# irda-usb-transmitter-V3.net
KiCad netlist of a schematic drawn in EAGLE
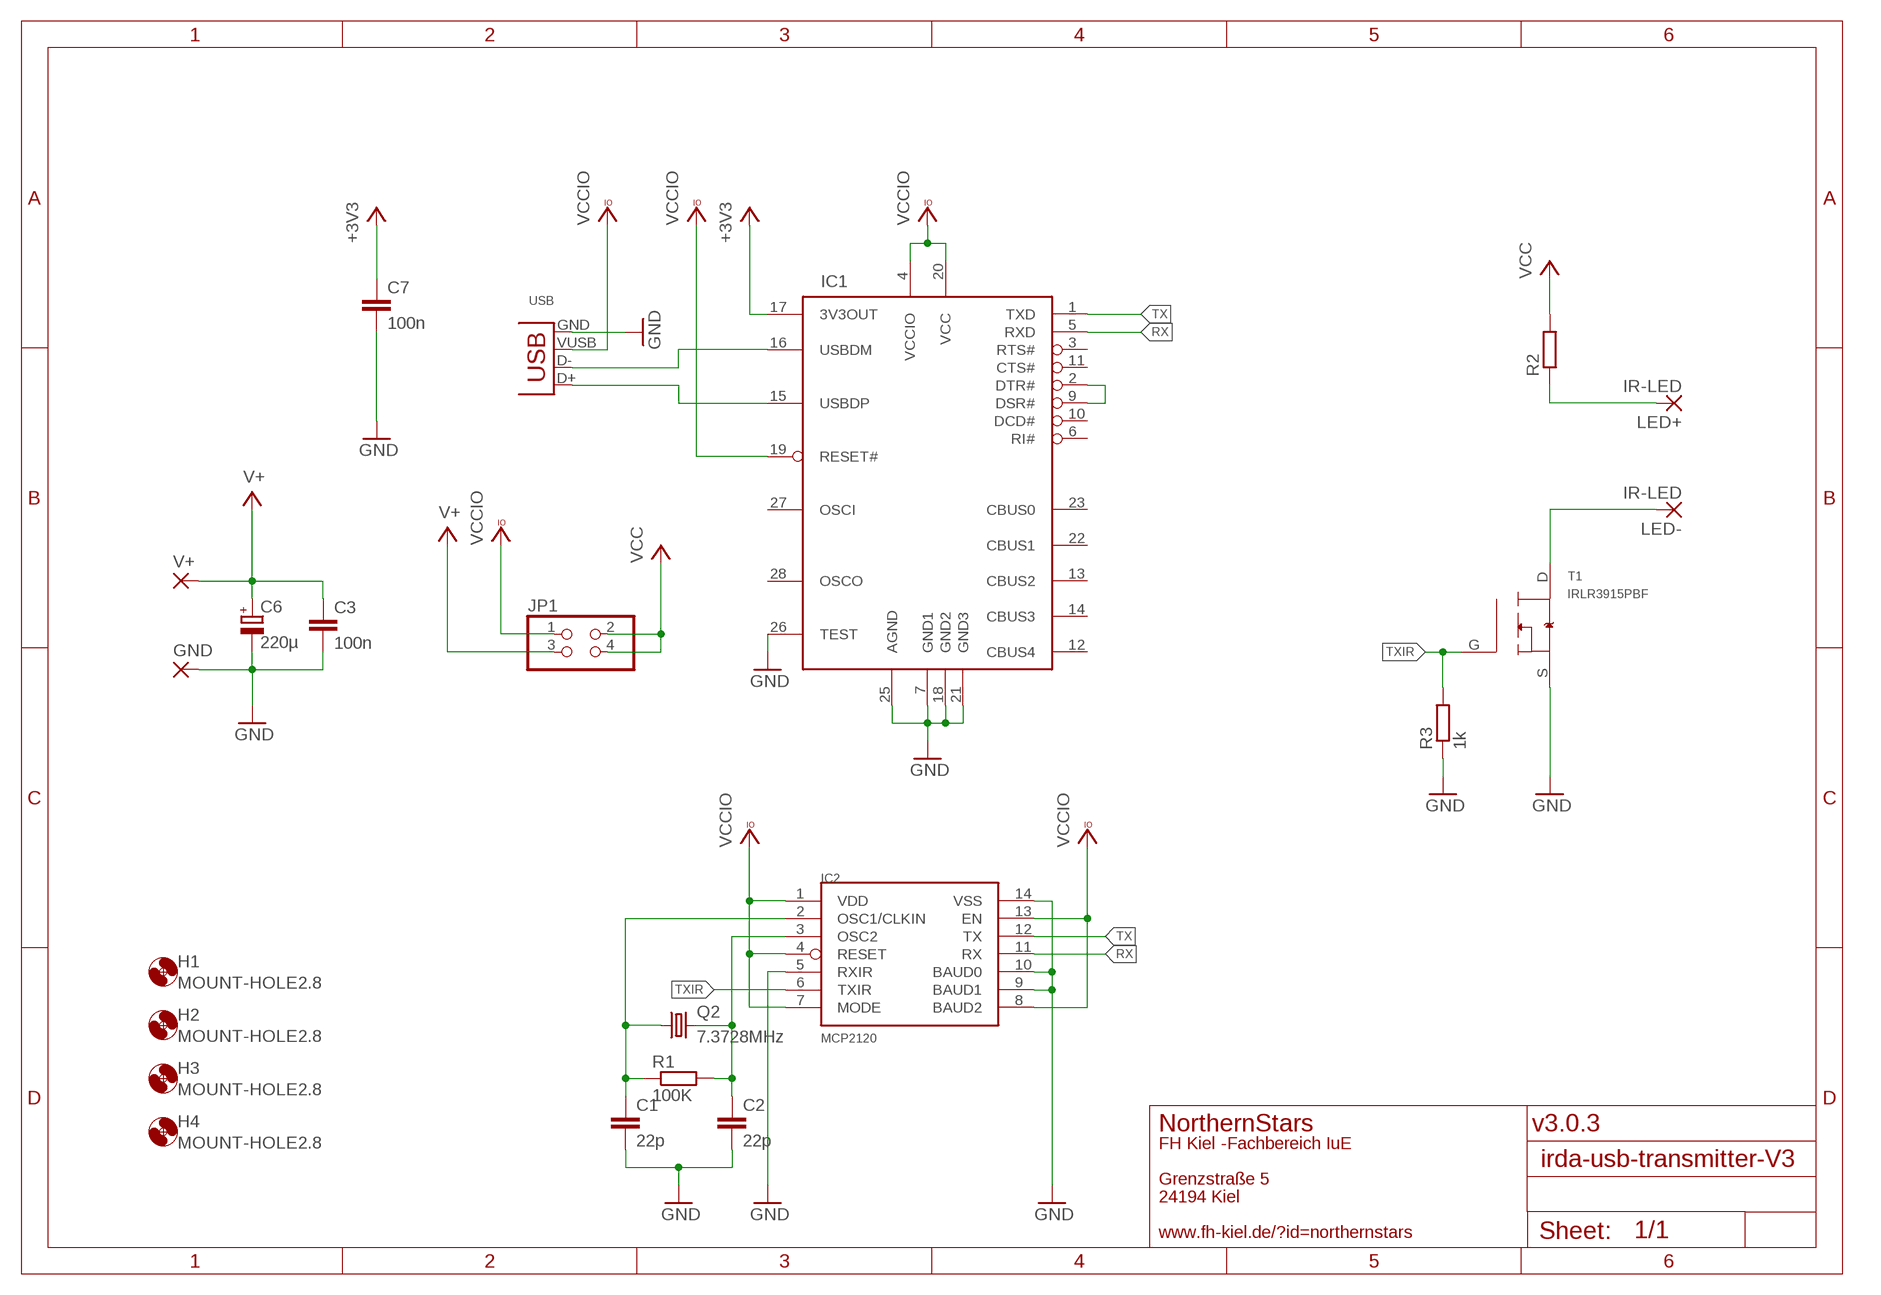
[diagram p0: schematic, sheet 1]

(export (version "E")
  (design (tool "Eeschema 10.0.6"))
  (components
    (comp (ref "C1")
      (value "22p")
      (footprint "eagle-import:C0805")
      (libsource (lib "eagle-import") (part "C-EUC0805"))
    )
    (comp (ref "C2")
      (value "22p")
      (footprint "eagle-import:C0805")
      (libsource (lib "eagle-import") (part "C-EUC0805"))
    )
    (comp (ref "C3")
      (value "100n")
      (footprint "eagle-import:C1206")
      (libsource (lib "eagle-import") (part "C-EUC1206"))
    )
    (comp (ref "C6")
      (value "220µ")
      (footprint "eagle-import:E3,5-8")
      (libsource (lib "eagle-import") (part "CPOL-EUE3.5-8"))
    )
    (comp (ref "C7")
      (value "100n")
      (footprint "eagle-import:C1206")
      (libsource (lib "eagle-import") (part "C-EUC1206"))
    )
    (comp (ref "GND")
      (value "SMD5")
      (footprint "eagle-import:SMD2,54-5,08")
      (libsource (lib "eagle-import") (part "SMD5"))
    )
    (comp (ref "H1")
      (value "MOUNT-HOLE2.8")
      (footprint "eagle-import:2,8")
      (libsource (lib "eagle-import") (part "MOUNT-HOLE2.8"))
    )
    (comp (ref "H2")
      (value "MOUNT-HOLE2.8")
      (footprint "eagle-import:2,8")
      (libsource (lib "eagle-import") (part "MOUNT-HOLE2.8"))
    )
    (comp (ref "H3")
      (value "MOUNT-HOLE2.8")
      (footprint "eagle-import:2,8")
      (libsource (lib "eagle-import") (part "MOUNT-HOLE2.8"))
    )
    (comp (ref "H4")
      (value "MOUNT-HOLE2.8")
      (footprint "eagle-import:2,8")
      (libsource (lib "eagle-import") (part "MOUNT-HOLE2.8"))
    )
    (comp (ref "IC1")
      (value "FT232RL")
      (footprint "eagle-import:SSOP28DB")
      (libsource (lib "eagle-import") (part "FT232RL"))
    )
    (comp (ref "IC2")
      (value "MCP2120")
      (footprint "eagle-import:SO-14")
      (libsource (lib "eagle-import") (part "MCP2120"))
    )
    (comp (ref "JP1")
      (value "PINHD-2X2")
      (footprint "eagle-import:2X02")
      (libsource (lib "eagle-import") (part "PINHD-2X2"))
    )
    (comp (ref "LED+")
      (value "IR-LED")
      (footprint "eagle-import:5-2,5")
      (libsource (lib "eagle-import") (part "WIREPADSMD5-2,5"))
    )
    (comp (ref "LED-")
      (value "IR-LED")
      (footprint "eagle-import:5-2,5")
      (libsource (lib "eagle-import") (part "WIREPADSMD5-2,5"))
    )
    (comp (ref "Q2")
      (value "7.3728MHz")
      (footprint "eagle-import:HC49UP")
      (libsource (lib "eagle-import") (part "CRYTALHC49UP"))
    )
    (comp (ref "R1")
      (value "100K")
      (footprint "eagle-import:R1206")
      (libsource (lib "eagle-import") (part "R-EU_R1206"))
    )
    (comp (ref "R2")
      (value "R-EU_R1206")
      (footprint "eagle-import:R1206")
      (libsource (lib "eagle-import") (part "R-EU_R1206"))
    )
    (comp (ref "R3")
      (value "1k")
      (footprint "eagle-import:R1206")
      (libsource (lib "eagle-import") (part "R-EU_R1206"))
    )
    (comp (ref "T1")
      (value "IRLR3915PBF")
      (footprint "eagle-import:D-PAK")
      (libsource (lib "eagle-import") (part "IRLR3915PBF"))
    )
    (comp (ref "USB")
      (value "USB-B-S")
      (footprint "eagle-import:USB-B-SMT")
      (libsource (lib "eagle-import") (part "USB-B-S"))
    )
    (comp (ref "V+")
      (value "SMD5")
      (footprint "eagle-import:SMD2,54-5,08")
      (libsource (lib "eagle-import") (part "SMD5"))
    )
  )
  (nets
    (net (code "1") (name "+3V3") (class "Default")
      (node (ref "C7") (pin "1") (pinfunction "1_1") (pintype "passive"))
      (node (ref "IC1") (pin "17") (pinfunction "3V3OUT_17") (pintype "output"))
    )
    (net (code "2") (name "GND") (class "Default")
      (node (ref "C1") (pin "2") (pinfunction "2_2") (pintype "passive"))
      (node (ref "C2") (pin "2") (pinfunction "2_2") (pintype "passive"))
      (node (ref "C3") (pin "2") (pinfunction "2_2") (pintype "passive"))
      (node (ref "C6") (pin "-") (pinfunction "-_-") (pintype "passive"))
      (node (ref "C7") (pin "2") (pinfunction "2_2") (pintype "passive"))
      (node (ref "GND") (pin "1") (pinfunction "P_1") (pintype "passive"))
      (node (ref "IC1") (pin "18") (pinfunction "GND2_18") (pintype "power_in"))
      (node (ref "IC1") (pin "21") (pinfunction "GND3_21") (pintype "power_in"))
      (node (ref "IC1") (pin "25") (pinfunction "AGND_25") (pintype "power_in"))
      (node (ref "IC1") (pin "26") (pinfunction "TEST_26") (pintype "input"))
      (node (ref "IC1") (pin "7") (pinfunction "GND1_7") (pintype "power_in"))
      (node (ref "IC2") (pin "10") (pinfunction "BAUD0_10") (pintype "bidirectional"))
      (node (ref "IC2") (pin "14") (pinfunction "VSS_14") (pintype "bidirectional"))
      (node (ref "IC2") (pin "5") (pinfunction "RXIR_5") (pintype "bidirectional"))
      (node (ref "IC2") (pin "9") (pinfunction "BAUD1_9") (pintype "bidirectional"))
      (node (ref "R3") (pin "1") (pinfunction "1_1") (pintype "passive"))
      (node (ref "T1") (pin "S") (pinfunction "P$3_S") (pintype "bidirectional"))
      (node (ref "USB") (pin "GND") (pinfunction "GND_GND") (pintype "bidirectional"))
    )
    (net (code "3") (name "Net-(IC1-DSR#)") (class "Default")
      (node (ref "IC1") (pin "2") (pinfunction "DTR#_2") (pintype "output"))
      (node (ref "IC1") (pin "9") (pinfunction "DSR#_9") (pintype "input"))
    )
    (net (code "4") (name "Net-(IC1-USBDM)") (class "Default")
      (node (ref "IC1") (pin "16") (pinfunction "USBDM_16") (pintype "bidirectional"))
      (node (ref "USB") (pin "D-") (pinfunction "D-_D-") (pintype "bidirectional"))
    )
    (net (code "5") (name "Net-(IC1-USBDP)") (class "Default")
      (node (ref "IC1") (pin "15") (pinfunction "USBDP_15") (pintype "bidirectional"))
      (node (ref "USB") (pin "D+") (pinfunction "D+_D+") (pintype "bidirectional"))
    )
    (net (code "6") (name "Net-(IC2-OSC1{slash}CLKIN)") (class "Default")
      (node (ref "C1") (pin "1") (pinfunction "1_1") (pintype "passive"))
      (node (ref "IC2") (pin "2") (pinfunction "OSC1/CLKIN_2") (pintype "bidirectional"))
      (node (ref "Q2") (pin "1") (pinfunction "1_1") (pintype "passive"))
      (node (ref "R1") (pin "1") (pinfunction "1_1") (pintype "passive"))
    )
    (net (code "7") (name "Net-(IC2-OSC2)") (class "Default")
      (node (ref "C2") (pin "1") (pinfunction "1_1") (pintype "passive"))
      (node (ref "IC2") (pin "3") (pinfunction "OSC2_3") (pintype "bidirectional"))
      (node (ref "Q2") (pin "2") (pinfunction "2_2") (pintype "passive"))
      (node (ref "R1") (pin "2") (pinfunction "2_2") (pintype "passive"))
    )
    (net (code "8") (name "Net-(LED+-P)") (class "Default")
      (node (ref "LED+") (pin "1") (pinfunction "P_1") (pintype "passive"))
      (node (ref "R2") (pin "1") (pinfunction "1_1") (pintype "passive"))
    )
    (net (code "9") (name "Net-(LED--P)") (class "Default")
      (node (ref "LED-") (pin "1") (pinfunction "P_1") (pintype "passive"))
      (node (ref "T1") (pin "D") (pinfunction "P$2_D") (pintype "bidirectional"))
    )
    (net (code "10") (name "RX") (class "Default")
      (node (ref "IC1") (pin "5") (pinfunction "RXD_5") (pintype "input"))
      (node (ref "IC2") (pin "11") (pinfunction "RX_11") (pintype "bidirectional"))
    )
    (net (code "11") (name "TX") (class "Default")
      (node (ref "IC1") (pin "1") (pinfunction "TXD_1") (pintype "output"))
      (node (ref "IC2") (pin "12") (pinfunction "TX_12") (pintype "bidirectional"))
    )
    (net (code "12") (name "TXIR") (class "Default")
      (node (ref "IC2") (pin "6") (pinfunction "TXIR_6") (pintype "bidirectional"))
      (node (ref "R3") (pin "2") (pinfunction "2_2") (pintype "passive"))
      (node (ref "T1") (pin "G") (pinfunction "G_G") (pintype "bidirectional"))
    )
    (net (code "13") (name "V+") (class "Default")
      (node (ref "C3") (pin "1") (pinfunction "1_1") (pintype "passive"))
      (node (ref "C6") (pin "+") (pinfunction "+_+") (pintype "passive"))
      (node (ref "JP1") (pin "3") (pinfunction "3_3") (pintype "passive"))
      (node (ref "V+") (pin "1") (pinfunction "P_1") (pintype "passive"))
    )
    (net (code "14") (name "VCC") (class "Default")
      (node (ref "JP1") (pin "2") (pinfunction "2_2") (pintype "passive"))
      (node (ref "JP1") (pin "4") (pinfunction "4_4") (pintype "passive"))
      (node (ref "R2") (pin "2") (pinfunction "2_2") (pintype "passive"))
    )
    (net (code "15") (name "VCCIO") (class "Default")
      (node (ref "IC1") (pin "19") (pinfunction "RESET#_19") (pintype "input"))
      (node (ref "IC1") (pin "20") (pinfunction "VCC_20") (pintype "power_in"))
      (node (ref "IC1") (pin "4") (pinfunction "VCCIO_4") (pintype "power_in"))
      (node (ref "IC2") (pin "1") (pinfunction "VDD_1") (pintype "bidirectional"))
      (node (ref "IC2") (pin "13") (pinfunction "EN_13") (pintype "bidirectional"))
      (node (ref "IC2") (pin "4") (pinfunction "RESET_4") (pintype "bidirectional"))
      (node (ref "IC2") (pin "7") (pinfunction "MODE_7") (pintype "bidirectional"))
      (node (ref "IC2") (pin "8") (pinfunction "BAUD2_8") (pintype "bidirectional"))
      (node (ref "JP1") (pin "1") (pinfunction "1_1") (pintype "passive"))
      (node (ref "USB") (pin "VUSB") (pinfunction "VBUS_VUSB") (pintype "bidirectional"))
    )
    (net (code "16") (name "unconnected-(IC1-CBUS0-Pad23)") (class "Default")
      (node (ref "IC1") (pin "23") (pinfunction "CBUS0_23") (pintype "bidirectional"))
    )
    (net (code "17") (name "unconnected-(IC1-CBUS1-Pad22)") (class "Default")
      (node (ref "IC1") (pin "22") (pinfunction "CBUS1_22") (pintype "bidirectional"))
    )
    (net (code "18") (name "unconnected-(IC1-CBUS2-Pad13)") (class "Default")
      (node (ref "IC1") (pin "13") (pinfunction "CBUS2_13") (pintype "bidirectional"))
    )
    (net (code "19") (name "unconnected-(IC1-CBUS3-Pad14)") (class "Default")
      (node (ref "IC1") (pin "14") (pinfunction "CBUS3_14") (pintype "bidirectional"))
    )
    (net (code "20") (name "unconnected-(IC1-CBUS4-Pad12)") (class "Default")
      (node (ref "IC1") (pin "12") (pinfunction "CBUS4_12") (pintype "bidirectional"))
    )
    (net (code "21") (name "unconnected-(IC1-CTS#-Pad11)") (class "Default")
      (node (ref "IC1") (pin "11") (pinfunction "CTS#_11") (pintype "input"))
    )
    (net (code "22") (name "unconnected-(IC1-DCD#-Pad10)") (class "Default")
      (node (ref "IC1") (pin "10") (pinfunction "DCD#_10") (pintype "input"))
    )
    (net (code "23") (name "unconnected-(IC1-OSCI-Pad27)") (class "Default")
      (node (ref "IC1") (pin "27") (pinfunction "OSCI_27") (pintype "input"))
    )
    (net (code "24") (name "unconnected-(IC1-OSCO-Pad28)") (class "Default")
      (node (ref "IC1") (pin "28") (pinfunction "OSCO_28") (pintype "output"))
    )
    (net (code "25") (name "unconnected-(IC1-RI#-Pad6)") (class "Default")
      (node (ref "IC1") (pin "6") (pinfunction "RI#_6") (pintype "input"))
    )
    (net (code "26") (name "unconnected-(IC1-RTS#-Pad3)") (class "Default")
      (node (ref "IC1") (pin "3") (pinfunction "RTS#_3") (pintype "output"))
    )
  )
)
